# Sheet1.net
KiCad netlist of a schematic drawn in Altium Designer
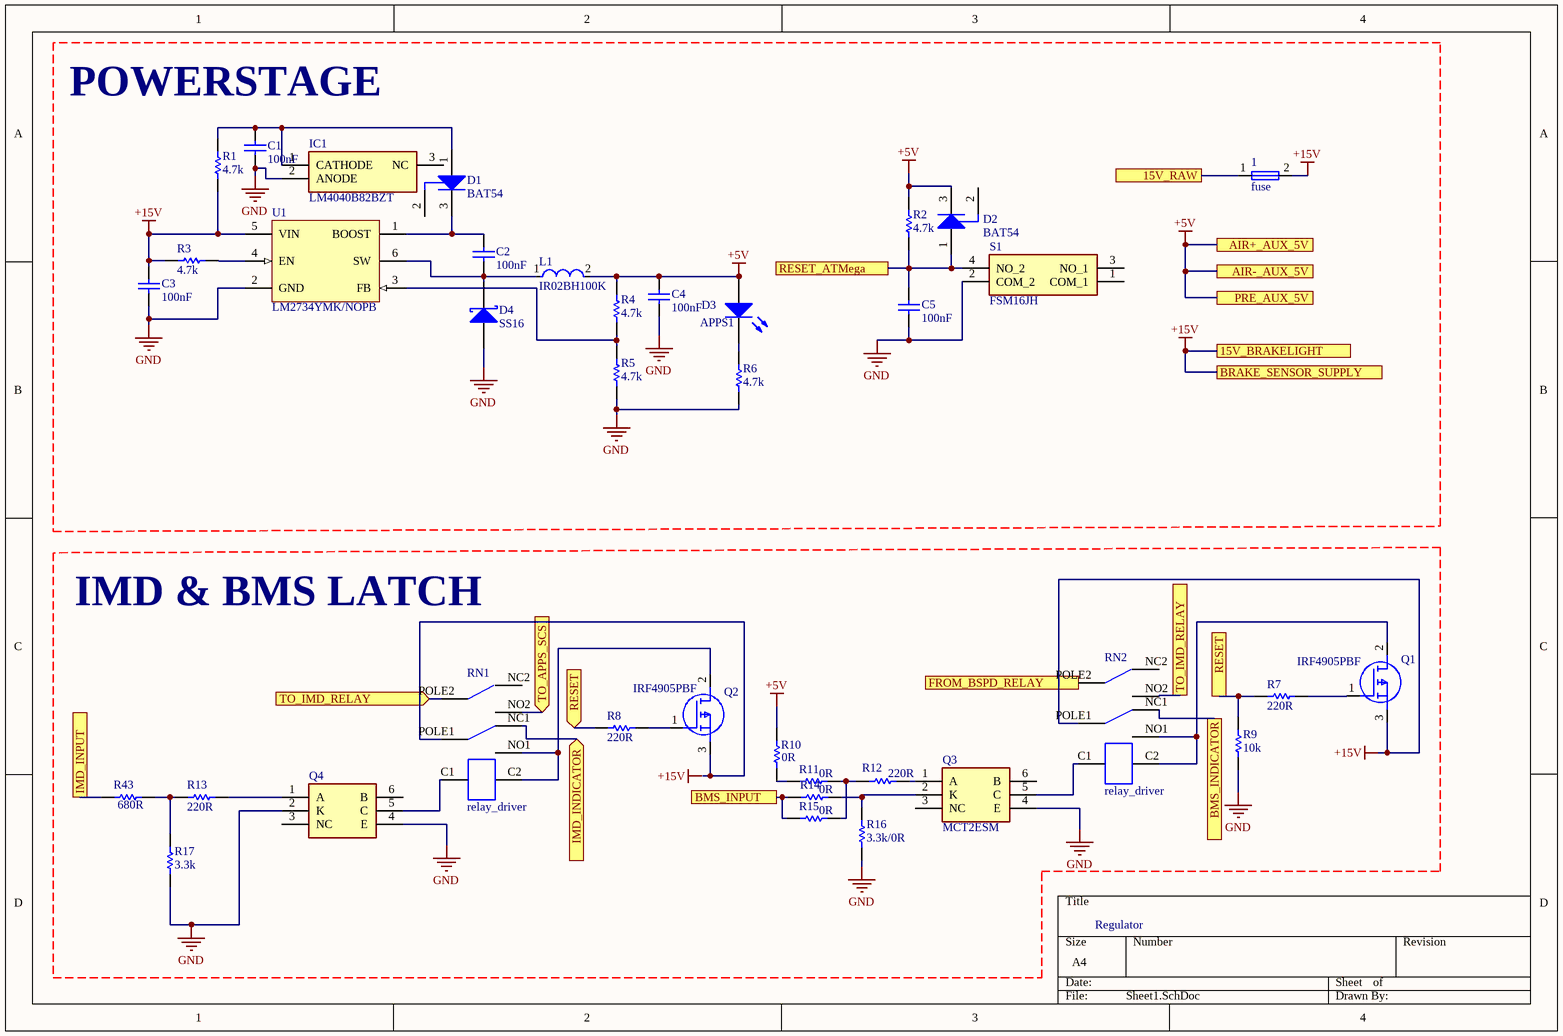
[diagram p0: Sheet1.SchDoc]

(export (version "E")
  (design (tool "Eeschema 10.0.6"))
  (components
    (comp (ref "1") (value "fuse") (footprint "fuse") (libsource (lib "Schlib1") (part "fuse")))
    (comp (ref "C1")
      (value "100nF")
      (footprint "KEMT-1206-2_N")
      (description "CAP, Ceramic, 0.1 uF, +/- 10%, 50 V, -55 to 125 degC, 1206 (3216 Metric), RoHS, Tape and Reel")
      (fields (field (name "MANUFACTURER") "Kemet"))
      (libsource (lib "Schlib1_TSAL_LV_3.1") (part "CMP-1037-04202-2"))
    )
    (comp (ref "C2")
      (value "100nF")
      (footprint "KEMT-1206-2_N")
      (description "CAP, Ceramic, 0.1 uF, +/- 10%, 50 V, -55 to 125 degC, 1206 (3216 Metric), RoHS, Tape and Reel")
      (fields (field (name "MANUFACTURER") "Kemet"))
      (libsource (lib "Schlib1_TSAL_LV_3.1") (part "CMP-1037-04202-2"))
    )
    (comp (ref "C3")
      (value "100nF")
      (footprint "KEMT-1206-2_N")
      (description "CAP, Ceramic, 0.1 uF, +/- 10%, 50 V, -55 to 125 degC, 1206 (3216 Metric), RoHS, Tape and Reel")
      (fields (field (name "MANUFACTURER") "Kemet"))
      (libsource (lib "Schlib1_TSAL_LV_3.1") (part "CMP-1037-04202-2"))
    )
    (comp (ref "C4")
      (value "100nF")
      (footprint "KEMT-1206-2_N")
      (description "CAP, Ceramic, 0.1 uF, +/- 10%, 50 V, -55 to 125 degC, 1206 (3216 Metric), RoHS, Tape and Reel")
      (fields (field (name "MANUFACTURER") "Kemet"))
      (libsource (lib "Schlib1_TSAL_LV_3.1") (part "CMP-1037-04202-2"))
    )
    (comp (ref "C5")
      (value "100nF")
      (footprint "KEMT-1206-2_N")
      (description "CAP, Ceramic, 0.1 uF, +/- 10%, 50 V, -55 to 125 degC, 1206 (3216 Metric), RoHS, Tape and Reel")
      (fields (field (name "MANUFACTURER") "Kemet"))
      (libsource (lib "Schlib1_TSAL_LV_3.1") (part "CMP-1037-04202-2"))
    )
    (comp (ref "D1")
      (value "BAT54")
      (footprint "INF-SOT23_N")
      (description "Silicon Schottky Diode, SOT23, Reel, Green")
      (fields (field (name "MANUFACTURER") "Infineon"))
      (libsource (lib "Schlib1_TSAL_LV_3.1") (part "CMP-1182-00010-1"))
    )
    (comp (ref "D2")
      (value "BAT54")
      (footprint "INF-SOT23_N")
      (description "Silicon Schottky Diode, SOT23, Reel, Green")
      (fields (field (name "MANUFACTURER") "Infineon"))
      (libsource (lib "Schlib1_TSAL_LV_3.1") (part "CMP-1182-00010-1"))
    )
    (comp (ref "D3")
      (value "APPS1")
      (footprint "3.2X1.6X1.1")
      (description "Typical RED, GREEN, YELLOW, AMBER GaAs LED")
      (fields (field (name "PUBLISHER") "Altium Limited"))
      (libsource (lib "Miscellaneous Devices") (part "LED2"))
    )
    (comp (ref "D4")
      (value "SS16")
      (footprint "FAIR-SMA-2_B_V")
      (description "Schottky Rectifier, 700 mV, -65 to 125 degC, 2-Pin SMA, RoHS, Tape and Reel")
      (fields (field (name "MANUFACTURER") "FairchildSemiconductor"))
      (libsource (lib "Schlib1") (part "CMP-2000-07149-1"))
    )
    (comp (ref "IC1")
      (value "LM4040B82BZT")
      (footprint "SamacSys:SOT95P237X112-3N")
      (description "Integrated Circuit")
      (fields
        (field (name "MANUFACTURER_PART_NUMBER") "LM4040B25IDBZT")
        (field (name "MOUSER PART NUMBER") "595-LM4040B25IDBZT")
      )
      (libsource (lib "*") (part "LM4040B25IDBZT"))
    )
    (comp (ref "L1")
      (value "IR02BH100K")
      (footprint "FP-IR02-MFG")
      (description "IR-2 10 10% B08")
      (fields (field (name "TOLERANCE") "10%") (field (name "OBSOLETE PART") "true"))
      (libsource (lib "Schlib1") (part "CMP-03630-000001-1"))
    )
    (comp (ref "Q1")
      (value "IRF4905PBF")
      (footprint "SamacSys:TO254P469X1042X1967-3P")
      (description "MOSFET (P-Channel)")
      (fields (field (name "MOUSER PART NUMBER") "942-IRF4905PBF"))
      (libsource (lib "*") (part "IRF4905PBF"))
    )
    (comp (ref "Q2")
      (value "IRF4905PBF")
      (footprint "SamacSys:TO254P469X1042X1967-3P")
      (description "MOSFET (P-Channel)")
      (fields (field (name "MOUSER PART NUMBER") "942-IRF4905PBF"))
      (libsource (lib "*") (part "IRF4905PBF"))
    )
    (comp (ref "Q3")
      (value "MCT2ESM")
      (footprint "SamacSys:SOT254P916X480-6N")
      (description "Phototransistor")
      (fields (field (name "MOUSER PART NUMBER") "512-MCT2ESM"))
      (libsource (lib "*") (part "MCT2ESM"))
    )
    (comp (ref "Q4")
      (value "MCT2ESM")
      (footprint "SamacSys:SOT254P916X480-6N")
      (description "Phototransistor")
      (fields (field (name "MOUSER PART NUMBER") "512-MCT2ESM"))
      (libsource (lib "*") (part "MCT2ESM"))
    )
    (comp (ref "R1")
      (value "4.7k")
      (footprint "R1206")
      (fields (field (name "PART NUMBER") "CRCW120647K0FKEA") (field (name "MANUFACTURER") "Vishay Dale"))
      (libsource (lib "Schlib1") (part "RES"))
    )
    (comp (ref "R2")
      (value "4.7k")
      (footprint "R1206")
      (fields (field (name "PART NUMBER") "CRCW120647K0FKEA") (field (name "MANUFACTURER") "Vishay Dale"))
      (libsource (lib "Schlib1") (part "RES"))
    )
    (comp (ref "R3")
      (value "4.7k")
      (footprint "R1206")
      (fields (field (name "PART NUMBER") "CRCW120647K0FKEA") (field (name "MANUFACTURER") "Vishay Dale"))
      (libsource (lib "Schlib1") (part "RES"))
    )
    (comp (ref "R4")
      (value "4.7k")
      (footprint "R1206")
      (fields (field (name "PART NUMBER") "CRCW120647K0FKEA") (field (name "MANUFACTURER") "Vishay Dale"))
      (libsource (lib "Schlib1") (part "RES"))
    )
    (comp (ref "R5")
      (value "4.7k")
      (footprint "R1206")
      (fields (field (name "PART NUMBER") "CRCW120647K0FKEA") (field (name "MANUFACTURER") "Vishay Dale"))
      (libsource (lib "Schlib1") (part "RES"))
    )
    (comp (ref "R6")
      (value "4.7k")
      (footprint "R1206")
      (fields (field (name "PART NUMBER") "CRCW120647K0FKEA") (field (name "MANUFACTURER") "Vishay Dale"))
      (libsource (lib "Schlib1") (part "RES"))
    )
    (comp (ref "R7")
      (value "220R")
      (footprint "R1206")
      (fields (field (name "PART NUMBER") "CRCW120647K0FKEA") (field (name "MANUFACTURER") "Vishay Dale"))
      (libsource (lib "Schlib1") (part "RES"))
    )
    (comp (ref "R8")
      (value "220R")
      (footprint "R1206")
      (fields (field (name "PART NUMBER") "CRCW120647K0FKEA") (field (name "MANUFACTURER") "Vishay Dale"))
      (libsource (lib "Schlib1") (part "RES"))
    )
    (comp (ref "R9")
      (value "10k")
      (footprint "R1206")
      (fields (field (name "PART NUMBER") "CRCW120647K0FKEA") (field (name "MANUFACTURER") "Vishay Dale"))
      (libsource (lib "Schlib1") (part "RES"))
    )
    (comp (ref "R10")
      (value "0R")
      (footprint "R1206")
      (fields (field (name "PART NUMBER") "CRCW120647K0FKEA") (field (name "MANUFACTURER") "Vishay Dale"))
      (libsource (lib "Schlib1") (part "RES"))
    )
    (comp (ref "R11")
      (value "0R")
      (footprint "R1206")
      (fields (field (name "PART NUMBER") "CRCW120647K0FKEA") (field (name "MANUFACTURER") "Vishay Dale"))
      (libsource (lib "Schlib1") (part "RES"))
    )
    (comp (ref "R12")
      (value "220R")
      (footprint "R1206")
      (fields (field (name "PART NUMBER") "CRCW120647K0FKEA") (field (name "MANUFACTURER") "Vishay Dale"))
      (libsource (lib "Schlib1") (part "RES"))
    )
    (comp (ref "R13")
      (value "220R")
      (footprint "R1206")
      (fields (field (name "PART NUMBER") "CRCW120647K0FKEA") (field (name "MANUFACTURER") "Vishay Dale"))
      (libsource (lib "Schlib1") (part "RES"))
    )
    (comp (ref "R14")
      (value "0R")
      (footprint "R1206")
      (fields (field (name "PART NUMBER") "CRCW120647K0FKEA") (field (name "MANUFACTURER") "Vishay Dale"))
      (libsource (lib "Schlib1") (part "RES"))
    )
    (comp (ref "R15")
      (value "0R")
      (footprint "R1206")
      (fields (field (name "PART NUMBER") "CRCW120647K0FKEA") (field (name "MANUFACTURER") "Vishay Dale"))
      (libsource (lib "Schlib1") (part "RES"))
    )
    (comp (ref "R16")
      (value "3.3k/0R")
      (footprint "R1206")
      (fields (field (name "PART NUMBER") "CRCW120647K0FKEA") (field (name "MANUFACTURER") "Vishay Dale"))
      (libsource (lib "Schlib1") (part "RES"))
    )
    (comp (ref "R17")
      (value "3.3k")
      (footprint "R1206")
      (fields (field (name "PART NUMBER") "CRCW120647K0FKEA") (field (name "MANUFACTURER") "Vishay Dale"))
      (libsource (lib "Schlib1") (part "RES"))
    )
    (comp (ref "R43")
      (value "680R")
      (footprint "R1206")
      (fields (field (name "PART NUMBER") "CRCW120647K0FKEA") (field (name "MANUFACTURER") "Vishay Dale"))
      (libsource (lib "Schlib1") (part "RES"))
    )
    (comp (ref "RN1")
      (value "relay_driver")
      (footprint "OMRON_12_RELAY")
      (libsource (lib "Schlib1") (part "relay_driver"))
    )
    (comp (ref "RN2")
      (value "relay_driver")
      (footprint "OMRON_12_RELAY")
      (libsource (lib "Schlib1") (part "relay_driver"))
    )
    (comp (ref "S1")
      (value "FSM16JH")
      (footprint "SamacSys:FSM16JH")
      (description "Switch")
      (fields (field (name "MOUSER PART NUMBER") "506-FSM16JH"))
      (libsource (lib "*") (part "FSM16JH"))
    )
    (comp (ref "U1")
      (value "LM2734YMK/NOPB")
      (footprint "DDC0006A_N")
      (description "1A Load Step-Down DC-DC Regulator, 6-pin Tiny SOT23, Pb-Free")
      (fields (field (name "MANUFACTURER") "Texas Instruments"))
      (libsource (lib "Schlib1") (part "CMP-0069-01201-3"))
    )
  )
  (nets
    (net (code "1") (name "+5V") (class "Default")
      (node (ref "C4") (pin "2") (pinfunction "2_2") (pintype "passive"))
      (node (ref "D2") (pin "3") (pinfunction "K_3") (pintype "passive"))
      (node (ref "D3") (pin "1") (pinfunction "A_1") (pintype "passive"))
      (node (ref "L1") (pin "2") (pinfunction "2_2") (pintype "passive"))
      (node (ref "R10") (pin "2") (pinfunction "2_2") (pintype "passive"))
      (node (ref "R2") (pin "2") (pinfunction "2_2") (pintype "passive"))
      (node (ref "R4") (pin "2") (pinfunction "2_2") (pintype "passive"))
    )
    (net (code "2") (name "+15V") (class "Default")
      (node (ref "1") (pin "2") (pinfunction "2_2") (pintype "passive"))
      (node (ref "C3") (pin "2") (pinfunction "2_2") (pintype "passive"))
      (node (ref "Q1") (pin "3") (pinfunction "S_3") (pintype "passive"))
      (node (ref "R1") (pin "2") (pinfunction "2_2") (pintype "passive"))
      (node (ref "R3") (pin "1") (pinfunction "1_1") (pintype "passive"))
      (node (ref "RN2") (pin "POLE1") (pinfunction "POLE1_POLE1") (pintype "passive"))
      (node (ref "U1") (pin "5") (pinfunction "VIN_5") (pintype "power_in"))
    )
    (net (code "3") (name "/15V_RAW") (class "Default")
      (node (ref "1") (pin "1") (pinfunction "1_1") (pintype "passive"))
    )
    (net (code "4") (name "/BMS_INDICATOR") (class "Default")
      (node (ref "RN2") (pin "NC1") (pinfunction "NC1_NC1") (pintype "passive"))
    )
    (net (code "5") (name "/BMS_INPUT") (class "Default")
      (node (ref "R14") (pin "1") (pinfunction "1_1") (pintype "passive"))
      (node (ref "R15") (pin "1") (pinfunction "1_1") (pintype "passive"))
    )
    (net (code "6") (name "/FROM_BSPD_RELAY") (class "Default")
      (node (ref "RN2") (pin "POLE2") (pinfunction "POLE2_POLE2") (pintype "passive"))
    )
    (net (code "7") (name "/IMD_INDICATOR") (class "Default")
      (node (ref "RN1") (pin "NC1") (pinfunction "NC1_NC1") (pintype "passive"))
    )
    (net (code "8") (name "/IMD_INPUT") (class "Default")
      (node (ref "R43") (pin "1") (pinfunction "1_1") (pintype "passive"))
    )
    (net (code "9") (name "/RESET") (class "Default")
      (node (ref "R7") (pin "1") (pinfunction "1_1") (pintype "passive"))
      (node (ref "R8") (pin "1") (pinfunction "1_1") (pintype "passive"))
      (node (ref "R9") (pin "2") (pinfunction "2_2") (pintype "passive"))
    )
    (net (code "10") (name "/RESET_ATMega") (class "Default")
      (node (ref "C5") (pin "2") (pinfunction "2_2") (pintype "passive"))
      (node (ref "D2") (pin "1") (pinfunction "A_1") (pintype "passive"))
      (node (ref "R2") (pin "1") (pinfunction "1_1") (pintype "passive"))
      (node (ref "S1") (pin "4") (pinfunction "NO_2_4") (pintype "passive"))
    )
    (net (code "11") (name "/TO_APPS_SCS") (class "Default")
      (node (ref "RN1") (pin "NO2") (pinfunction "NO2_NO2") (pintype "passive"))
    )
    (net (code "12") (name "/TO_IMD_RELAY") (class "Default")
      (node (ref "RN1") (pin "POLE2") (pinfunction "POLE2_POLE2") (pintype "passive"))
      (node (ref "RN2") (pin "NO2") (pinfunction "NO2_NO2") (pintype "passive"))
    )
    (net (code "13") (name "GND") (class "Default")
      (node (ref "C1") (pin "1") (pinfunction "1_1") (pintype "passive"))
      (node (ref "C3") (pin "1") (pinfunction "1_1") (pintype "passive"))
      (node (ref "C4") (pin "1") (pinfunction "1_1") (pintype "passive"))
      (node (ref "C5") (pin "1") (pinfunction "1_1") (pintype "passive"))
      (node (ref "D4") (pin "1") (pinfunction "A_1") (pintype "passive"))
      (node (ref "IC1") (pin "2") (pinfunction "ANODE_2") (pintype "passive"))
      (node (ref "Q3") (pin "4") (pinfunction "E_4") (pintype "passive"))
      (node (ref "Q4") (pin "2") (pinfunction "K_2") (pintype "passive"))
      (node (ref "Q4") (pin "4") (pinfunction "E_4") (pintype "passive"))
      (node (ref "R16") (pin "1") (pinfunction "1_1") (pintype "passive"))
      (node (ref "R17") (pin "1") (pinfunction "1_1") (pintype "passive"))
      (node (ref "R5") (pin "1") (pinfunction "1_1") (pintype "passive"))
      (node (ref "R6") (pin "1") (pinfunction "1_1") (pintype "passive"))
      (node (ref "R9") (pin "1") (pinfunction "1_1") (pintype "passive"))
      (node (ref "S1") (pin "2") (pinfunction "COM_2_2") (pintype "passive"))
      (node (ref "U1") (pin "2") (pinfunction "GND_2") (pintype "power_in"))
    )
    (net (code "14") (name "Net-(D1-A)") (class "Default")
      (node (ref "C1") (pin "2") (pinfunction "2_2") (pintype "passive"))
      (node (ref "D1") (pin "1") (pinfunction "A_1") (pintype "passive"))
      (node (ref "IC1") (pin "1") (pinfunction "CATHODE_1") (pintype "passive"))
      (node (ref "R1") (pin "1") (pinfunction "1_1") (pintype "passive"))
    )
    (net (code "15") (name "Net-(D1-K)") (class "Default")
      (node (ref "C2") (pin "2") (pinfunction "2_2") (pintype "passive"))
      (node (ref "D1") (pin "3") (pinfunction "K_3") (pintype "passive"))
      (node (ref "U1") (pin "1") (pinfunction "BOOST_1") (pintype "passive"))
    )
    (net (code "16") (name "Net-(D3-K)") (class "Default")
      (node (ref "D3") (pin "2") (pinfunction "K_2") (pintype "passive"))
      (node (ref "R6") (pin "2") (pinfunction "2_2") (pintype "passive"))
    )
    (net (code "17") (name "Net-(D4-K)") (class "Default")
      (node (ref "C2") (pin "1") (pinfunction "1_1") (pintype "passive"))
      (node (ref "D4") (pin "2") (pinfunction "K_2") (pintype "passive"))
      (node (ref "L1") (pin "1") (pinfunction "1_1") (pintype "passive"))
      (node (ref "U1") (pin "6") (pinfunction "SW_6") (pintype "power_in"))
    )
    (net (code "18") (name "Net-(Q1-D)") (class "Default")
      (node (ref "Q1") (pin "2") (pinfunction "D_2") (pintype "passive"))
      (node (ref "RN2") (pin "C2") (pinfunction "C2_C2") (pintype "passive"))
      (node (ref "RN2") (pin "NO1") (pinfunction "NO1_NO1") (pintype "passive"))
    )
    (net (code "19") (name "Net-(Q1-G)") (class "Default")
      (node (ref "Q1") (pin "1") (pinfunction "G_1") (pintype "passive"))
      (node (ref "R7") (pin "2") (pinfunction "2_2") (pintype "passive"))
    )
    (net (code "20") (name "Net-(Q2-D)") (class "Default")
      (node (ref "Q2") (pin "2") (pinfunction "D_2") (pintype "passive"))
      (node (ref "RN1") (pin "C2") (pinfunction "C2_C2") (pintype "passive"))
      (node (ref "RN1") (pin "NO1") (pinfunction "NO1_NO1") (pintype "passive"))
    )
    (net (code "21") (name "Net-(Q2-G)") (class "Default")
      (node (ref "Q2") (pin "1") (pinfunction "G_1") (pintype "passive"))
      (node (ref "R8") (pin "2") (pinfunction "2_2") (pintype "passive"))
    )
    (net (code "22") (name "Net-(Q2-S)") (class "Default")
      (node (ref "Q2") (pin "3") (pinfunction "S_3") (pintype "passive"))
      (node (ref "RN1") (pin "POLE1") (pinfunction "POLE1_POLE1") (pintype "passive"))
    )
    (net (code "23") (name "Net-(Q3-A)") (class "Default")
      (node (ref "Q3") (pin "1") (pinfunction "A_1") (pintype "passive"))
      (node (ref "R12") (pin "2") (pinfunction "2_2") (pintype "passive"))
    )
    (net (code "24") (name "Net-(Q3-C)") (class "Default")
      (node (ref "Q3") (pin "5") (pinfunction "C_5") (pintype "passive"))
      (node (ref "RN2") (pin "C1") (pinfunction "C1_C1") (pintype "passive"))
    )
    (net (code "25") (name "Net-(Q3-K)") (class "Default")
      (node (ref "Q3") (pin "2") (pinfunction "K_2") (pintype "passive"))
      (node (ref "R14") (pin "2") (pinfunction "2_2") (pintype "passive"))
      (node (ref "R16") (pin "2") (pinfunction "2_2") (pintype "passive"))
    )
    (net (code "26") (name "Net-(Q4-A)") (class "Default")
      (node (ref "Q4") (pin "1") (pinfunction "A_1") (pintype "passive"))
      (node (ref "R13") (pin "2") (pinfunction "2_2") (pintype "passive"))
    )
    (net (code "27") (name "Net-(Q4-C)") (class "Default")
      (node (ref "Q4") (pin "5") (pinfunction "C_5") (pintype "passive"))
      (node (ref "RN1") (pin "C1") (pinfunction "C1_C1") (pintype "passive"))
    )
    (net (code "28") (name "Net-(R10-Pad1)") (class "Default")
      (node (ref "R10") (pin "1") (pinfunction "1_1") (pintype "passive"))
      (node (ref "R11") (pin "1") (pinfunction "1_1") (pintype "passive"))
    )
    (net (code "29") (name "Net-(R11-Pad2)") (class "Default")
      (node (ref "R11") (pin "2") (pinfunction "2_2") (pintype "passive"))
      (node (ref "R12") (pin "1") (pinfunction "1_1") (pintype "passive"))
      (node (ref "R15") (pin "2") (pinfunction "2_2") (pintype "passive"))
    )
    (net (code "30") (name "Net-(R13-Pad1)") (class "Default")
      (node (ref "R13") (pin "1") (pinfunction "1_1") (pintype "passive"))
      (node (ref "R17") (pin "2") (pinfunction "2_2") (pintype "passive"))
      (node (ref "R43") (pin "2") (pinfunction "2_2") (pintype "passive"))
    )
    (net (code "31") (name "Net-(U1-EN)") (class "Default")
      (node (ref "R3") (pin "2") (pinfunction "2_2") (pintype "passive"))
      (node (ref "U1") (pin "4") (pinfunction "EN_4") (pintype "input"))
    )
    (net (code "32") (name "Net-(U1-FB)") (class "Default")
      (node (ref "R4") (pin "1") (pinfunction "1_1") (pintype "passive"))
      (node (ref "R5") (pin "2") (pinfunction "2_2") (pintype "passive"))
      (node (ref "U1") (pin "3") (pinfunction "FB_3") (pintype "input"))
    )
    (net (code "33") (name "unconnected-(D1-NC-Pad2)") (class "Default")
      (node (ref "D1") (pin "2") (pinfunction "NC_2") (pintype "passive"))
    )
    (net (code "34") (name "unconnected-(D2-NC-Pad2)") (class "Default")
      (node (ref "D2") (pin "2") (pinfunction "NC_2") (pintype "passive"))
    )
    (net (code "35") (name "unconnected-(IC1-NC-Pad3)") (class "Default")
      (node (ref "IC1") (pin "3") (pinfunction "NC_3") (pintype "passive"))
    )
    (net (code "36") (name "unconnected-(Q3-B-Pad6)") (class "Default")
      (node (ref "Q3") (pin "6") (pinfunction "B_6") (pintype "passive"))
    )
    (net (code "37") (name "unconnected-(Q3-NC-Pad3)") (class "Default")
      (node (ref "Q3") (pin "3") (pinfunction "NC_3") (pintype "passive"))
    )
    (net (code "38") (name "unconnected-(Q4-B-Pad6)") (class "Default")
      (node (ref "Q4") (pin "6") (pinfunction "B_6") (pintype "passive"))
    )
    (net (code "39") (name "unconnected-(Q4-NC-Pad3)") (class "Default")
      (node (ref "Q4") (pin "3") (pinfunction "NC_3") (pintype "passive"))
    )
    (net (code "40") (name "unconnected-(RN1-PadNC2)") (class "Default")
      (node (ref "RN1") (pin "NC2") (pinfunction "NC2_NC2") (pintype "passive"))
    )
    (net (code "41") (name "unconnected-(RN2-PadNC2)") (class "Default")
      (node (ref "RN2") (pin "NC2") (pinfunction "NC2_NC2") (pintype "passive"))
    )
    (net (code "42") (name "unconnected-(S1-COM_1-Pad1)") (class "Default")
      (node (ref "S1") (pin "1") (pinfunction "COM_1_1") (pintype "passive"))
    )
    (net (code "43") (name "unconnected-(S1-NO_1-Pad3)") (class "Default")
      (node (ref "S1") (pin "3") (pinfunction "NO_1_3") (pintype "passive"))
    )
  )
)
